# 28PinArduino.net
KiCad netlist of a schematic drawn in Altium Designer
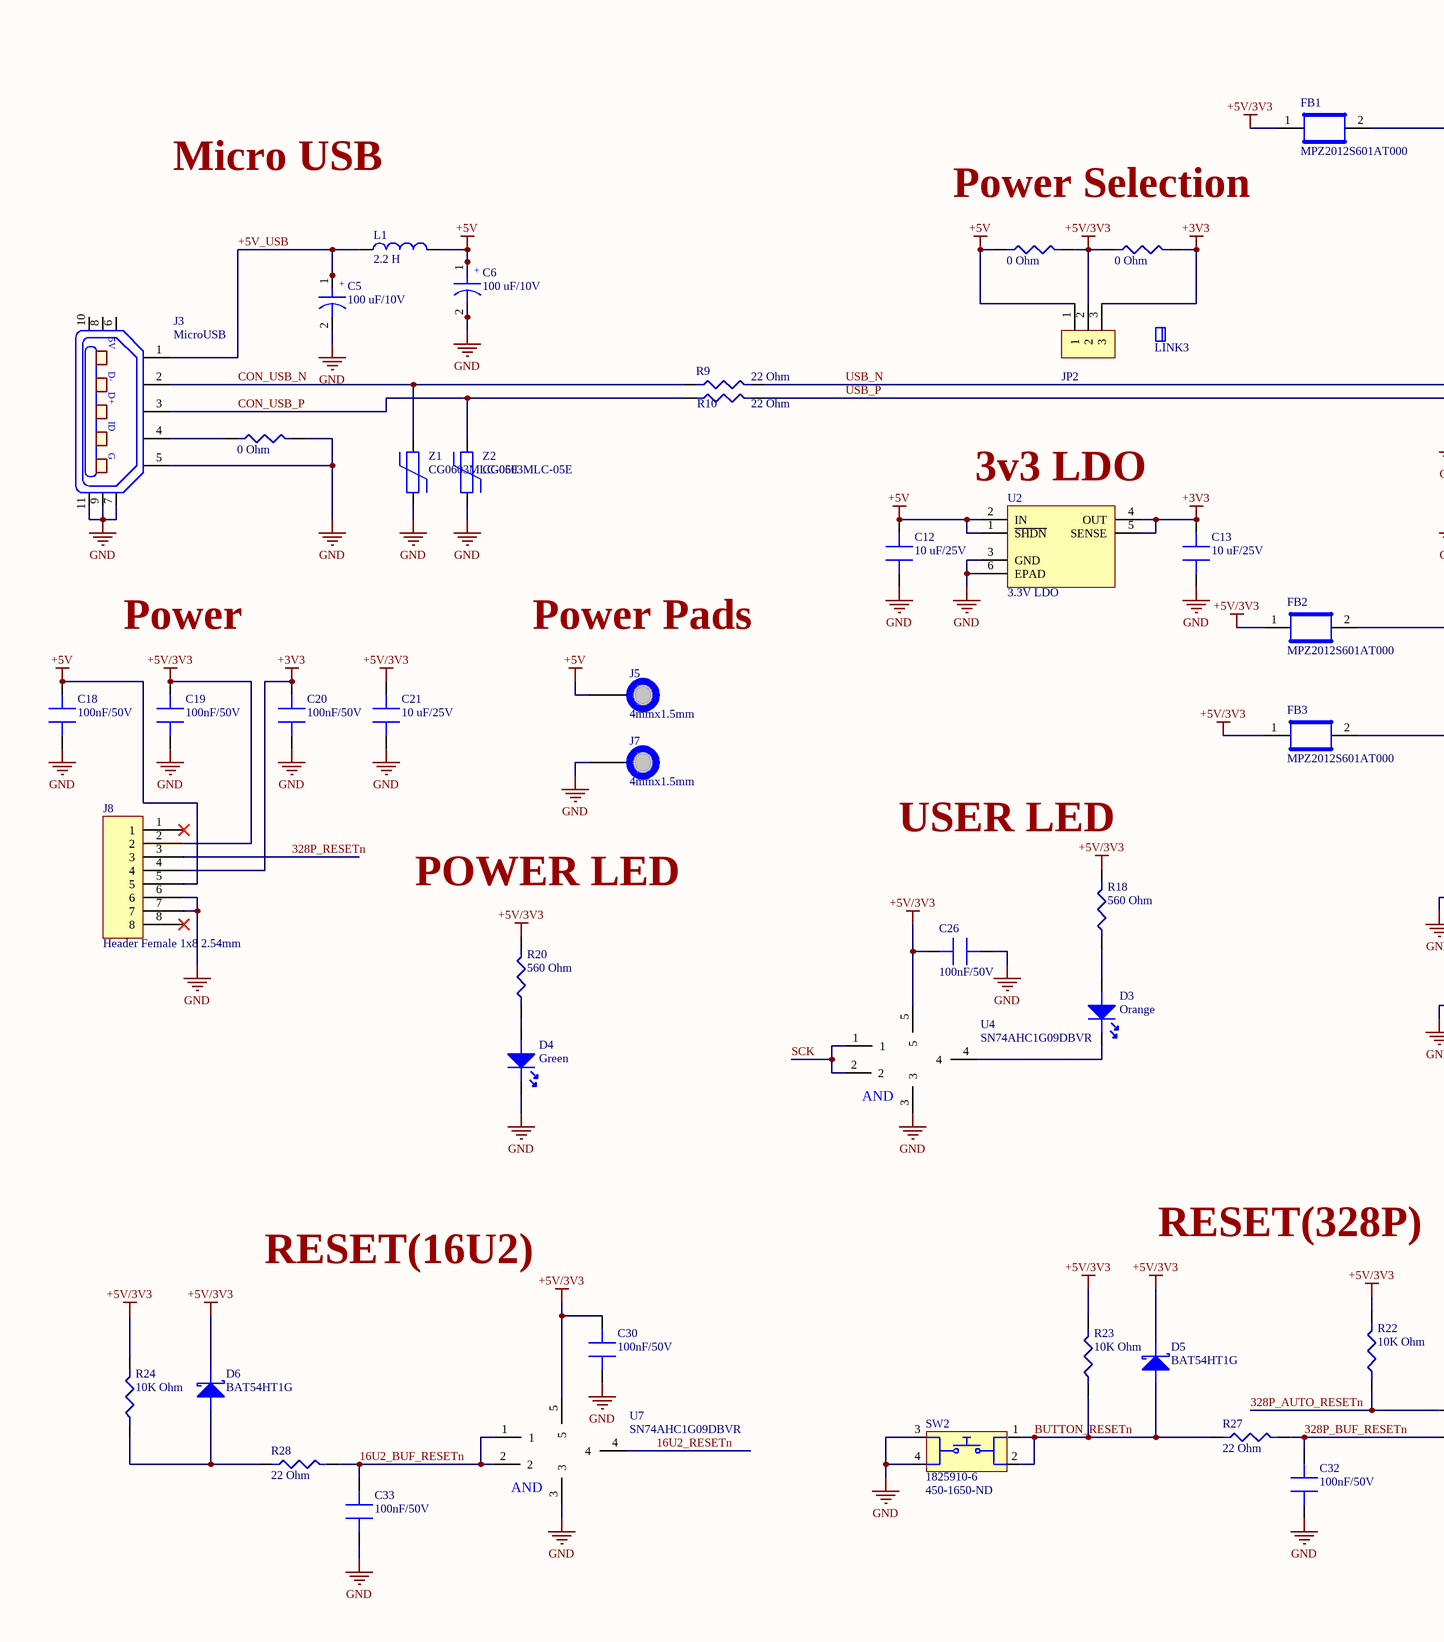
[diagram p0: 28PinArduino.SchDoc, left]
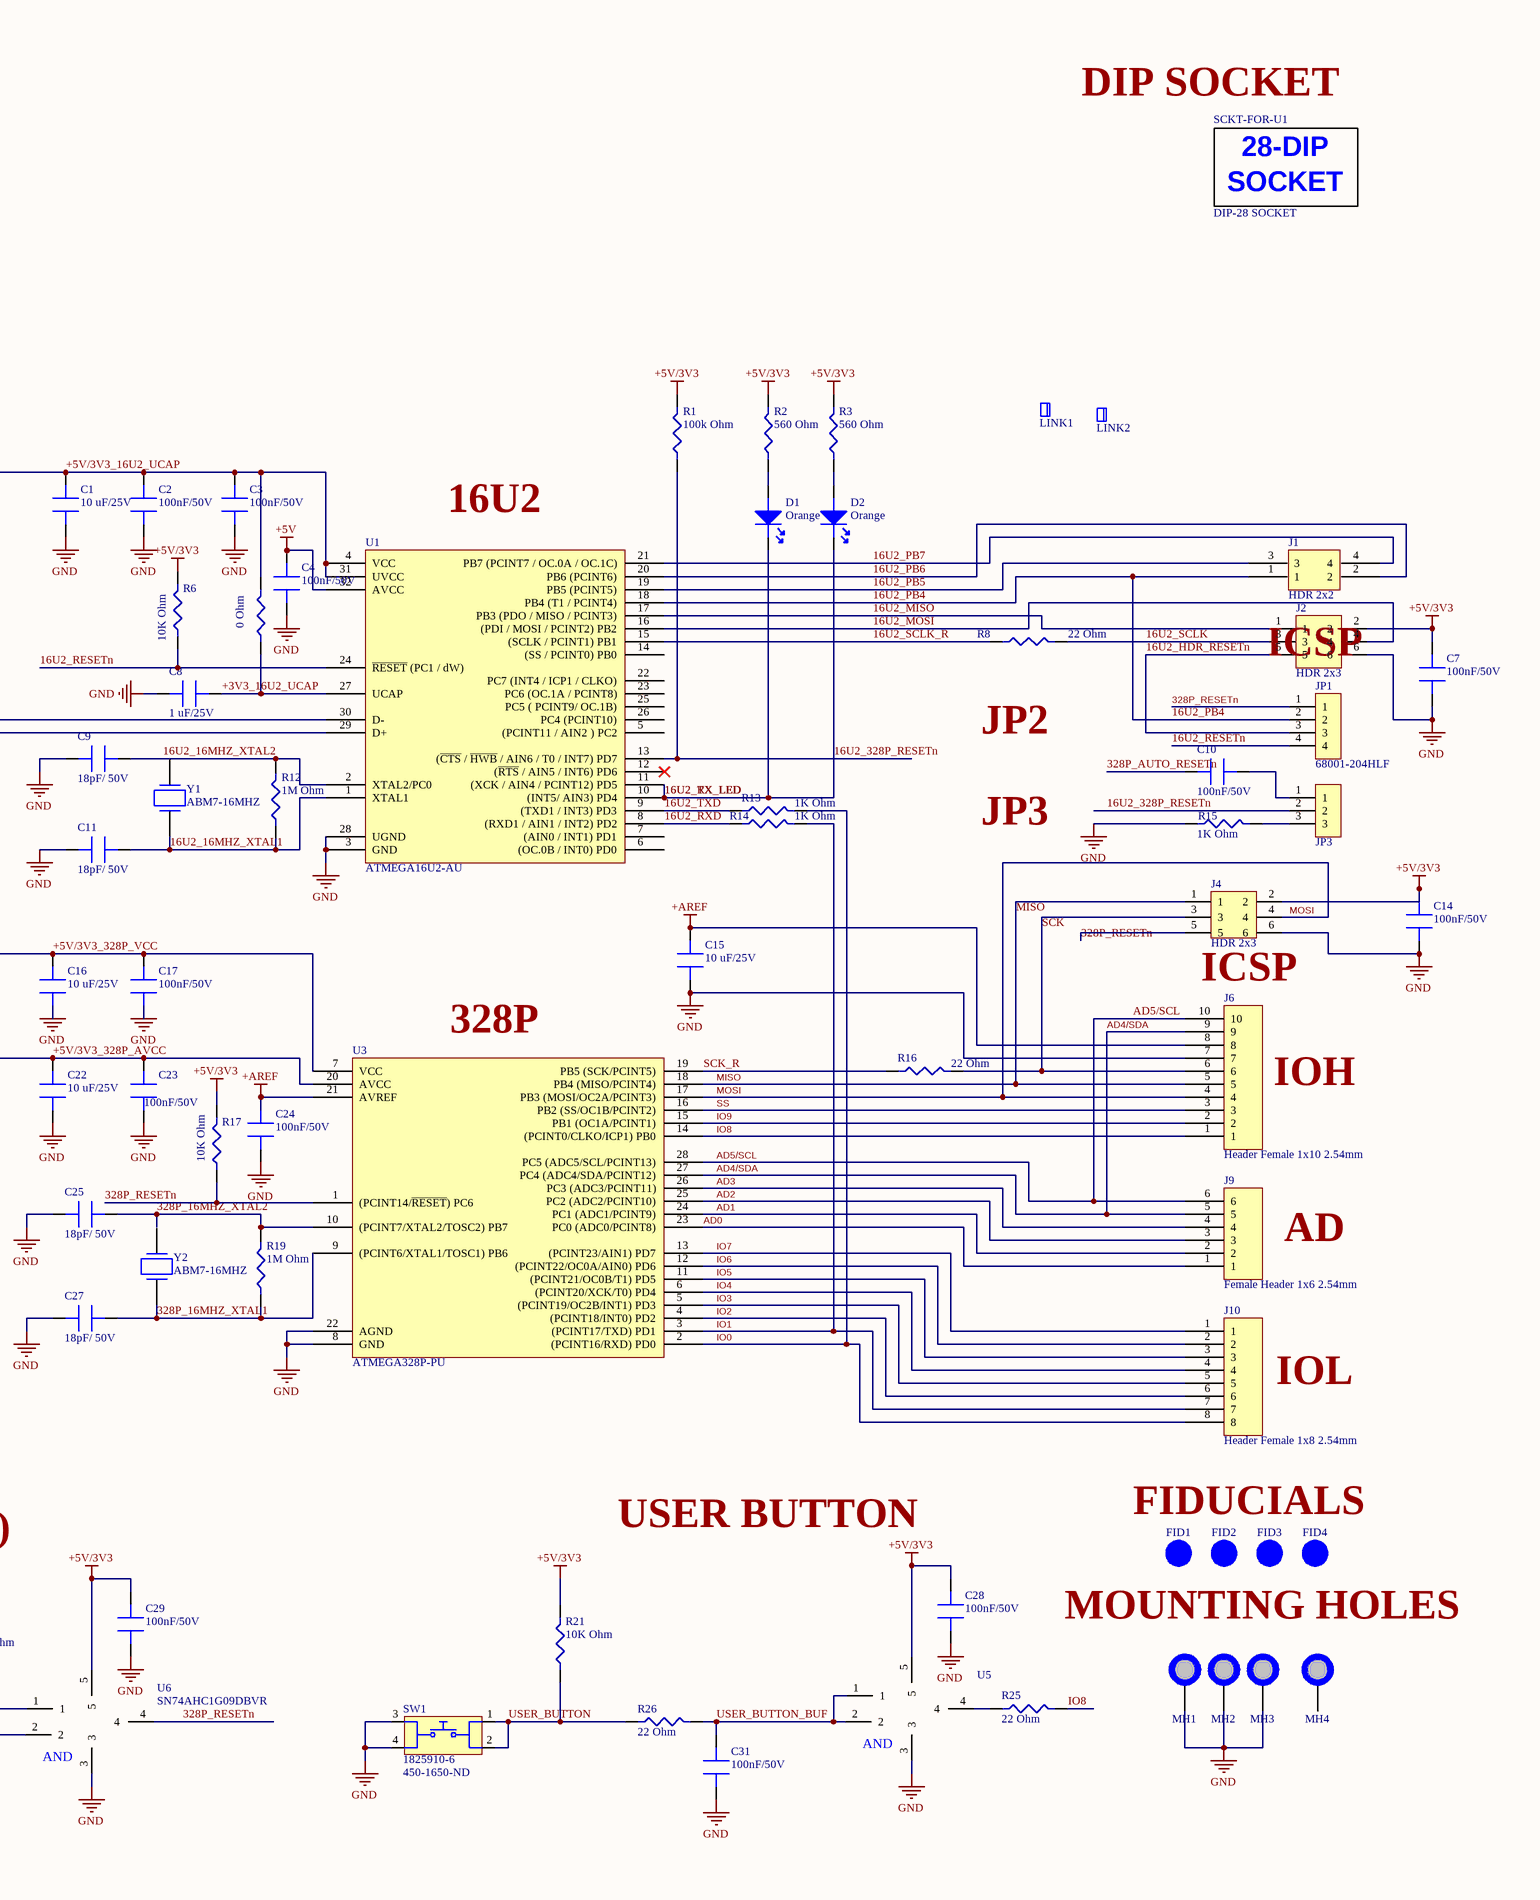
[diagram p1: 28PinArduino.SchDoc, right]

(export (version "E")
  (design (tool "Eeschema 10.0.6"))
  (components
    (comp (ref "C1")
      (value "10 uF/25V")
      (footprint "CAPC2012X14N")
      (fields
        (field (name "MANUFACTURER") "TDK")
        (field (name "MANUFACTURER PART NUMBER") "C2012X5R1E106K125AB")
        (field (name "TOLERANCE") "10%")
      )
      (libsource (lib "28PinArduino") (part "C2012X5R1E106K125AB"))
    )
    (comp (ref "C2")
      (value "100nF/50V")
      (footprint "CAPC2012X14N")
      (fields
        (field (name "MANUFACTURER") "TDK")
        (field (name "MANUFACTURER PART NUMBER") "C2012X7R1H104K085AA")
        (field (name "TOLERANCE") "10%")
      )
      (libsource (lib "28PinArduino") (part "C2012X7R1H104K085AA"))
    )
    (comp (ref "C3")
      (value "100nF/50V")
      (footprint "CAPC2012X14N")
      (fields
        (field (name "MANUFACTURER") "TDK")
        (field (name "MANUFACTURER PART NUMBER") "C2012X7R1H104K085AA")
        (field (name "TOLERANCE") "10%")
      )
      (libsource (lib "28PinArduino") (part "C2012X7R1H104K085AA"))
    )
    (comp (ref "C4")
      (value "100nF/50V")
      (footprint "CAPC2012X14N")
      (fields
        (field (name "MANUFACTURER") "TDK")
        (field (name "MANUFACTURER PART NUMBER") "C2012X7R1H104K085AA")
        (field (name "TOLERANCE") "10%")
      )
      (libsource (lib "28PinArduino") (part "C2012X7R1H104K085AA"))
    )
    (comp (ref "C5")
      (value "100 uF/10V")
      (footprint "C_ALU_C_SIZE")
      (description "Cap Aluminum 100uF 10V 20% (5 X 5.4mm) SMD 50mA 1000 hr 85°C T/R")
      (fields
        (field (name "MANUFACTURER") "Panasonic")
        (field (name "MANUFACTURER PART NUMBER") "EEE-1AA101WR")
      )
      (libsource (lib "28PinArduino") (part "EEE-1AA101WR"))
    )
    (comp (ref "C6")
      (value "100 uF/10V")
      (footprint "C_ALU_C_SIZE")
      (description "Cap Aluminum 100uF 10V 20% (5 X 5.4mm) SMD 50mA 1000 hr 85°C T/R")
      (fields
        (field (name "MANUFACTURER") "Panasonic")
        (field (name "MANUFACTURER PART NUMBER") "EEE-1AA101WR")
      )
      (libsource (lib "28PinArduino") (part "EEE-1AA101WR"))
    )
    (comp (ref "C7")
      (value "100nF/50V")
      (footprint "CAPC2012X14N")
      (fields
        (field (name "MANUFACTURER") "TDK")
        (field (name "MANUFACTURER PART NUMBER") "C2012X7R1H104K085AA")
        (field (name "TOLERANCE") "10%")
      )
      (libsource (lib "28PinArduino") (part "C2012X7R1H104K085AA"))
    )
    (comp (ref "C8")
      (value "1 uF/25V")
      (footprint "CAPC2012X14N")
      (fields
        (field (name "MANUFACTURER") "TDK")
        (field (name "MANUFACTURER PART NUMBER") "C2012X5R1E105K125AA")
        (field (name "TOLERANCE") "10%")
      )
      (libsource (lib "28PinArduino") (part "C2012X5R1E105K125AA"))
    )
    (comp (ref "C9")
      (value "18pF/ 50V")
      (footprint "CAPC2012X14N")
      (description "CAP CER 18PF 50V C0G/NP0 0805")
      (fields
        (field (name "MANUFACTURER") "KEMET")
        (field (name "MANUFACTURER PART NUMBER") "C0805C180J5GACTU")
      )
      (libsource (lib "28PinArduino") (part "C0805C180J5GACTU"))
    )
    (comp (ref "C10")
      (value "100nF/50V")
      (footprint "CAPC2012X14N")
      (fields
        (field (name "MANUFACTURER") "TDK")
        (field (name "MANUFACTURER PART NUMBER") "C2012X7R1H104K085AA")
        (field (name "TOLERANCE") "10%")
      )
      (libsource (lib "28PinArduino") (part "C2012X7R1H104K085AA"))
    )
    (comp (ref "C11")
      (value "18pF/ 50V")
      (footprint "CAPC2012X14N")
      (description "CAP CER 18PF 50V C0G/NP0 0805")
      (fields
        (field (name "MANUFACTURER") "KEMET")
        (field (name "MANUFACTURER PART NUMBER") "C0805C180J5GACTU")
      )
      (libsource (lib "28PinArduino") (part "C0805C180J5GACTU"))
    )
    (comp (ref "C12")
      (value "10 uF/25V")
      (footprint "CAPC2012X14N")
      (fields
        (field (name "MANUFACTURER") "TDK")
        (field (name "MANUFACTURER PART NUMBER") "C2012X5R1E106K125AB")
        (field (name "TOLERANCE") "10%")
      )
      (libsource (lib "28PinArduino") (part "C2012X5R1E106K125AB"))
    )
    (comp (ref "C13")
      (value "10 uF/25V")
      (footprint "CAPC2012X14N")
      (fields
        (field (name "MANUFACTURER") "TDK")
        (field (name "MANUFACTURER PART NUMBER") "C2012X5R1E106K125AB")
        (field (name "TOLERANCE") "10%")
      )
      (libsource (lib "28PinArduino") (part "C2012X5R1E106K125AB"))
    )
    (comp (ref "C14")
      (value "100nF/50V")
      (footprint "CAPC2012X14N")
      (fields
        (field (name "MANUFACTURER") "TDK")
        (field (name "MANUFACTURER PART NUMBER") "C2012X7R1H104K085AA")
        (field (name "TOLERANCE") "10%")
      )
      (libsource (lib "28PinArduino") (part "C2012X7R1H104K085AA"))
    )
    (comp (ref "C15")
      (value "10 uF/25V")
      (footprint "CAPC2012X14N")
      (fields
        (field (name "MANUFACTURER") "TDK")
        (field (name "MANUFACTURER PART NUMBER") "C2012X5R1E106K125AB")
        (field (name "TOLERANCE") "10%")
      )
      (libsource (lib "28PinArduino") (part "C2012X5R1E106K125AB"))
    )
    (comp (ref "C16")
      (value "10 uF/25V")
      (footprint "CAPC2012X14N")
      (fields
        (field (name "MANUFACTURER") "TDK")
        (field (name "MANUFACTURER PART NUMBER") "C2012X5R1E106K125AB")
        (field (name "TOLERANCE") "10%")
      )
      (libsource (lib "28PinArduino") (part "C2012X5R1E106K125AB"))
    )
    (comp (ref "C17")
      (value "100nF/50V")
      (footprint "CAPC2012X14N")
      (fields
        (field (name "MANUFACTURER") "TDK")
        (field (name "MANUFACTURER PART NUMBER") "C2012X7R1H104K085AA")
        (field (name "TOLERANCE") "10%")
      )
      (libsource (lib "28PinArduino") (part "C2012X7R1H104K085AA"))
    )
    (comp (ref "C18")
      (value "100nF/50V")
      (footprint "CAPC2012X14N")
      (fields
        (field (name "MANUFACTURER") "TDK")
        (field (name "MANUFACTURER PART NUMBER") "C2012X7R1H104K085AA")
        (field (name "TOLERANCE") "10%")
      )
      (libsource (lib "28PinArduino") (part "C2012X7R1H104K085AA"))
    )
    (comp (ref "C19")
      (value "100nF/50V")
      (footprint "CAPC2012X14N")
      (fields
        (field (name "MANUFACTURER") "TDK")
        (field (name "MANUFACTURER PART NUMBER") "C2012X7R1H104K085AA")
        (field (name "TOLERANCE") "10%")
      )
      (libsource (lib "28PinArduino") (part "C2012X7R1H104K085AA"))
    )
    (comp (ref "C20")
      (value "100nF/50V")
      (footprint "CAPC2012X14N")
      (fields
        (field (name "MANUFACTURER") "TDK")
        (field (name "MANUFACTURER PART NUMBER") "C2012X7R1H104K085AA")
        (field (name "TOLERANCE") "10%")
      )
      (libsource (lib "28PinArduino") (part "C2012X7R1H104K085AA"))
    )
    (comp (ref "C21")
      (value "10 uF/25V")
      (footprint "CAPC2012X14N")
      (fields
        (field (name "MANUFACTURER") "TDK")
        (field (name "MANUFACTURER PART NUMBER") "C2012X5R1E106K125AB")
        (field (name "TOLERANCE") "10%")
      )
      (libsource (lib "28PinArduino") (part "C2012X5R1E106K125AB"))
    )
    (comp (ref "C22")
      (value "10 uF/25V")
      (footprint "CAPC2012X14N")
      (fields
        (field (name "MANUFACTURER") "TDK")
        (field (name "MANUFACTURER PART NUMBER") "C2012X5R1E106K125AB")
        (field (name "TOLERANCE") "10%")
      )
      (libsource (lib "28PinArduino") (part "C2012X5R1E106K125AB"))
    )
    (comp (ref "C23")
      (value "100nF/50V")
      (footprint "CAPC2012X14N")
      (fields
        (field (name "MANUFACTURER") "TDK")
        (field (name "MANUFACTURER PART NUMBER") "C2012X7R1H104K085AA")
        (field (name "TOLERANCE") "10%")
      )
      (libsource (lib "28PinArduino") (part "C2012X7R1H104K085AA"))
    )
    (comp (ref "C24")
      (value "100nF/50V")
      (footprint "CAPC2012X14N")
      (fields
        (field (name "MANUFACTURER") "TDK")
        (field (name "MANUFACTURER PART NUMBER") "C2012X7R1H104K085AA")
        (field (name "TOLERANCE") "10%")
      )
      (libsource (lib "28PinArduino") (part "C2012X7R1H104K085AA"))
    )
    (comp (ref "C25")
      (value "18pF/ 50V")
      (footprint "CAPC2012X14N")
      (description "CAP CER 18PF 50V C0G/NP0 0805")
      (fields
        (field (name "MANUFACTURER") "KEMET")
        (field (name "MANUFACTURER PART NUMBER") "C0805C180J5GACTU")
      )
      (libsource (lib "28PinArduino") (part "C0805C180J5GACTU"))
    )
    (comp (ref "C26")
      (value "100nF/50V")
      (footprint "CAPC2012X14N")
      (fields
        (field (name "MANUFACTURER") "TDK")
        (field (name "MANUFACTURER PART NUMBER") "C2012X7R1H104K085AA")
        (field (name "TOLERANCE") "10%")
      )
      (libsource (lib "28PinArduino") (part "C2012X7R1H104K085AA"))
    )
    (comp (ref "C27")
      (value "18pF/ 50V")
      (footprint "CAPC2012X14N")
      (description "CAP CER 18PF 50V C0G/NP0 0805")
      (fields
        (field (name "MANUFACTURER") "KEMET")
        (field (name "MANUFACTURER PART NUMBER") "C0805C180J5GACTU")
      )
      (libsource (lib "28PinArduino") (part "C0805C180J5GACTU"))
    )
    (comp (ref "C28")
      (value "100nF/50V")
      (footprint "CAPC2012X14N")
      (fields
        (field (name "MANUFACTURER") "TDK")
        (field (name "MANUFACTURER PART NUMBER") "C2012X7R1H104K085AA")
        (field (name "TOLERANCE") "10%")
      )
      (libsource (lib "28PinArduino") (part "C2012X7R1H104K085AA"))
    )
    (comp (ref "C29")
      (value "100nF/50V")
      (footprint "CAPC2012X14N")
      (fields
        (field (name "MANUFACTURER") "TDK")
        (field (name "MANUFACTURER PART NUMBER") "C2012X7R1H104K085AA")
        (field (name "TOLERANCE") "10%")
      )
      (libsource (lib "28PinArduino") (part "C2012X7R1H104K085AA"))
    )
    (comp (ref "C30")
      (value "100nF/50V")
      (footprint "CAPC2012X14N")
      (fields
        (field (name "MANUFACTURER") "TDK")
        (field (name "MANUFACTURER PART NUMBER") "C2012X7R1H104K085AA")
        (field (name "TOLERANCE") "10%")
      )
      (libsource (lib "28PinArduino") (part "C2012X7R1H104K085AA"))
    )
    (comp (ref "C31")
      (value "100nF/50V")
      (footprint "CAPC2012X14N")
      (fields
        (field (name "MANUFACTURER") "TDK")
        (field (name "MANUFACTURER PART NUMBER") "C2012X7R1H104K085AA")
        (field (name "TOLERANCE") "10%")
      )
      (libsource (lib "28PinArduino") (part "C2012X7R1H104K085AA"))
    )
    (comp (ref "C32")
      (value "100nF/50V")
      (footprint "CAPC2012X14N")
      (fields
        (field (name "MANUFACTURER") "TDK")
        (field (name "MANUFACTURER PART NUMBER") "C2012X7R1H104K085AA")
        (field (name "TOLERANCE") "10%")
      )
      (libsource (lib "28PinArduino") (part "C2012X7R1H104K085AA"))
    )
    (comp (ref "C33")
      (value "100nF/50V")
      (footprint "CAPC2012X14N")
      (fields
        (field (name "MANUFACTURER") "TDK")
        (field (name "MANUFACTURER PART NUMBER") "C2012X7R1H104K085AA")
        (field (name "TOLERANCE") "10%")
      )
      (libsource (lib "28PinArduino") (part "C2012X7R1H104K085AA"))
    )
    (comp (ref "D1")
      (value "Orange")
      (footprint "LED0603")
      (description "OSRAM - LO L29K-H2K1-24-Z - SMARTLED 0603 ORANGE")
      (fields
        (field (name "MANUFACTURER") "Osram Opto")
        (field (name "MANUFACTURER PART NUMBER") "LOL29K-H2K1-24-Z")
      )
      (libsource (lib "28PinArduino") (part "LOL29K-H2K1-24-Z"))
    )
    (comp (ref "D2")
      (value "Orange")
      (footprint "LED0603")
      (description "OSRAM - LO L29K-H2K1-24-Z - SMARTLED 0603 ORANGE")
      (fields
        (field (name "MANUFACTURER") "Osram Opto")
        (field (name "MANUFACTURER PART NUMBER") "LOL29K-H2K1-24-Z")
      )
      (libsource (lib "28PinArduino") (part "LOL29K-H2K1-24-Z"))
    )
    (comp (ref "D3")
      (value "Orange")
      (footprint "LED0603")
      (description "OSRAM - LO L29K-H2K1-24-Z - SMARTLED 0603 ORANGE")
      (fields
        (field (name "MANUFACTURER") "Osram Opto")
        (field (name "MANUFACTURER PART NUMBER") "LOL29K-H2K1-24-Z")
      )
      (libsource (lib "28PinArduino") (part "LOL29K-H2K1-24-Z"))
    )
    (comp (ref "D4")
      (value "Green")
      (footprint "LED0603")
      (description "LED Uni-Color Green 572nm 2-Pin Chip 0603(1608Metric) T/R")
      (fields
        (field (name "MANUFACTURER") "Osram Opto")
        (field (name "MANUFACTURER PART NUMBER") "LGL29K-G2J1-24-Z")
      )
      (libsource (lib "28PinArduino") (part "LGL29K-G2J1-24-Z"))
    )
    (comp (ref "D5")
      (value "BAT54HT1G")
      (footprint "Diode_SOD323")
      (description "Small Signal Schottky Diode, Single, 30 V, 200 mA, 800 mV, 600 mA, 150 C ;RoHS Compliant: Yes")
      (fields (field (name "MANUFACTURER") "ON Semiconductor / Fairchild"))
      (libsource (lib "28PinArduino") (part "BAT54HT1G"))
    )
    (comp (ref "D6")
      (value "BAT54HT1G")
      (footprint "Diode_SOD323")
      (description "Small Signal Schottky Diode, Single, 30 V, 200 mA, 800 mV, 600 mA, 150 C ;RoHS Compliant: Yes")
      (fields (field (name "MANUFACTURER") "ON Semiconductor / Fairchild"))
      (libsource (lib "28PinArduino") (part "BAT54HT1G"))
    )
    (comp (ref "FB1")
      (value "MPZ2012S601AT000")
      (footprint "CAPC2012X14N")
      (description "FERRITE BEAD 600 OHM 0805 1LN")
      (fields (field (name "MANUFACTURER") "TDK"))
      (libsource (lib "28PinArduino") (part "MPZ2012S601AT000"))
    )
    (comp (ref "FB2")
      (value "MPZ2012S601AT000")
      (footprint "CAPC2012X14N")
      (description "FERRITE BEAD 600 OHM 0805 1LN")
      (fields (field (name "MANUFACTURER") "TDK"))
      (libsource (lib "28PinArduino") (part "MPZ2012S601AT000"))
    )
    (comp (ref "FB3")
      (value "MPZ2012S601AT000")
      (footprint "CAPC2012X14N")
      (description "FERRITE BEAD 600 OHM 0805 1LN")
      (fields (field (name "MANUFACTURER") "TDK"))
      (libsource (lib "28PinArduino") (part "MPZ2012S601AT000"))
    )
    (comp (ref "FID1")
      (value "FID_1mm")
      (footprint "FID_40X1_20D")
      (description "Fiducial 40 mil Diameter 120mil Mask")
      (libsource (lib "28PinArduino") (part "FID_1mm"))
    )
    (comp (ref "FID2")
      (value "FID_1mm")
      (footprint "FID_40X1_20D")
      (description "Fiducial 40 mil Diameter 120mil Mask")
      (libsource (lib "28PinArduino") (part "FID_1mm"))
    )
    (comp (ref "FID3")
      (value "FID_1mm")
      (footprint "FID_40X1_20D")
      (description "Fiducial 40 mil Diameter 120mil Mask")
      (libsource (lib "28PinArduino") (part "FID_1mm"))
    )
    (comp (ref "FID4")
      (value "FID_1mm")
      (footprint "FID_40X1_20D")
      (description "Fiducial 40 mil Diameter 120mil Mask")
      (libsource (lib "28PinArduino") (part "FID_1mm"))
    )
    (comp (ref "J1")
      (value "HDR 2x2")
      (fields
        (field (name "MANUFACTURER") "Amphenol ICC / FCI")
        (field (name "MANUFACTURER PART NUMBER") "68602-204HLF")
      )
      (libsource (lib "28PinArduino") (part "68602-204HLF"))
    )
    (comp (ref "J2")
      (value "HDR 2x3")
      (footprint "DIP6")
      (description "CONN HEADER 6POS .100 STR 30AU")
      (fields
        (field (name "MANUFACTURER") "Amphenol FCI")
        (field (name "MANUFACTURER PART NUMBER") "67997-106HLF")
      )
      (libsource (lib "") (part "67997-106HLF_1"))
    )
    (comp (ref "J3")
      (value "MicroUSB")
      (footprint "microUSB")
      (description "CONN USB MICRO B RECPT SMT R/A")
      (fields
        (field (name "MANUFACTURER") "Amphenol FCI")
        (field (name "MANUFACTURER PART NUMBER") "10118193-0001LF")
      )
      (libsource (lib "28PinArduino") (part "10118193-0001LF"))
    )
    (comp (ref "J4")
      (value "HDR 2x3")
      (footprint "DIP6")
      (description "CONN HEADER 6POS .100 STR 30AU")
      (fields
        (field (name "MANUFACTURER") "Amphenol FCI")
        (field (name "MANUFACTURER PART NUMBER") "67997-106HLF")
      )
      (libsource (lib "28PinArduino") (part "67997-106HLF"))
    )
    (comp (ref "J5")
      (value "4mmx1.5mm")
      (footprint "PAD_WITH_HOLE")
      (description "Pad with a hole")
      (libsource (lib "28PinArduino") (part "PAD_WITH_HOLE"))
    )
    (comp (ref "J6")
      (value "Header Female 1x10 2.54mm")
      (footprint "DIP20")
      (fields (field (name "MANUFACTURER") "Harwin") (field (name "MANUFACTURER PART NUMBER") "M20-7821046"))
      (libsource (lib "28PinArduino") (part "M20-7821046"))
    )
    (comp (ref "J7")
      (value "4mmx1.5mm")
      (footprint "PAD_WITH_HOLE")
      (description "Pad with a hole")
      (libsource (lib "28PinArduino") (part "PAD_WITH_HOLE"))
    )
    (comp (ref "J8")
      (value "Header Female 1x8 2.54mm")
      (footprint "DIP16")
      (description "2.54mm (0.1\") Pitch SIL Vertical PC Tail Socket Assembly, selective gold + tin, 8 contacts")
      (fields (field (name "MANUFACTURER") "Harwin") (field (name "MANUFACTURER PART NUMBER") "M20-7820842"))
      (libsource (lib "") (part "M20-7820842_1"))
    )
    (comp (ref "J9")
      (value "Female Header 1x6 2.54mm")
      (footprint "DIP12")
      (description "06-WAY SIL VERT SOCKET L/FREE")
      (fields (field (name "MANUFACTURER") "Harwin") (field (name "MANUFACTURER PART NUMBER") "M20-7820646"))
      (libsource (lib "28PinArduino") (part "M20-7820646"))
    )
    (comp (ref "J10")
      (value "Header Female 1x8 2.54mm")
      (footprint "DIP16")
      (description "2.54mm (0.1\") Pitch SIL Vertical PC Tail Socket Assembly, selective gold + tin, 8 contacts")
      (fields (field (name "MANUFACTURER") "Harwin") (field (name "MANUFACTURER PART NUMBER") "M20-7820842"))
      (libsource (lib "28PinArduino") (part "M20-7820842"))
    )
    (comp (ref "JP1")
      (value "68001-204HLF")
      (footprint "DIP1x4")
      (description "CONN HEADER VERT 4POS 2.54MM")
      (fields (field (name "MANUFACTURER") "Amphenol FCI"))
      (libsource (lib "28PinArduino") (part "68001-204HLF"))
    )
    (comp (ref "JP2")
      (value "68000-103HLF")
      (footprint "DIP1x3")
      (fields (field (name "MANUFACTURER") "Amphenol ICC"))
      (libsource (lib "28PinArduino") (part "68000-103HLF"))
    )
    (comp (ref "JP3")
      (value "68000-103HLF")
      (footprint "DIP1x3")
      (fields (field (name "MANUFACTURER") "Amphenol ICC"))
      (libsource (lib "") (part "68000-103HLF_1"))
    )
    (comp (ref "L1")
      (value "2.2 H")
      (footprint "L1210")
      (description "FIXED IND 2.2UH 2A 80 MOHM SMD")
      (fields
        (field (name "MANUFACTURER") "KEMET")
        (field (name "MANUFACTURER PART NUMBER") "L1210R2R2MDWIT")
      )
      (libsource (lib "28PinArduino") (part "L1210R2R2MDWIT"))
    )
    (comp (ref "LINK1")
      (value "Link")
      (description "CONN JUMPER SHORTING .100\" GOLD")
      (fields
        (field (name "MANUFACTURER") "Sullins")
        (field (name "MANUFACTURER PART NUMBER") "QPC02SXGN-RC")
      )
      (libsource (lib "28PinArduino") (part "QPC02SXGN-RC"))
    )
    (comp (ref "LINK2")
      (value "Link")
      (description "CONN JUMPER SHORTING .100\" GOLD")
      (fields
        (field (name "MANUFACTURER") "Sullins")
        (field (name "MANUFACTURER PART NUMBER") "QPC02SXGN-RC")
      )
      (libsource (lib "28PinArduino") (part "QPC02SXGN-RC"))
    )
    (comp (ref "LINK3")
      (value "Link")
      (description "CONN JUMPER SHORTING .100\" GOLD")
      (fields
        (field (name "MANUFACTURER") "Sullins")
        (field (name "MANUFACTURER PART NUMBER") "QPC02SXGN-RC")
      )
      (libsource (lib "28PinArduino") (part "QPC02SXGN-RC"))
    )
    (comp (ref "MH1")
      (value "MH_7.4MMC_3.2")
      (footprint "MH_7.4mm_3.2mm")
      (description "Mounting Hole 7.4mm diameter, 3.2 mm drill")
      (libsource (lib "28PinArduino") (part "MH_7.4MMC_3.2"))
    )
    (comp (ref "MH2")
      (value "MH_7.4MMC_3.2")
      (footprint "MH_7.4mm_3.2mm")
      (description "Mounting Hole 7.4mm diameter, 3.2 mm drill")
      (libsource (lib "28PinArduino") (part "MH_7.4MMC_3.2"))
    )
    (comp (ref "MH3")
      (value "MH_7.4MMC_3.2")
      (footprint "MH_7.4mm_3.2mm")
      (description "Mounting Hole 7.4mm diameter, 3.2 mm drill")
      (libsource (lib "28PinArduino") (part "MH_7.4MMC_3.2"))
    )
    (comp (ref "MH4")
      (value "MH_7.4MMC_3")
      (footprint "MH_7.4mm_3.2mm")
      (description "Mounting Hole Non Copper 7.4mm diameter 3mm drill NPTH")
      (libsource (lib "28PinArduino") (part "MH_7.4MMNC_3.2MMD"))
    )
    (comp (ref "R1")
      (value "100k Ohm")
      (footprint "RESC2012X06N")
      (description "YAGEO         RC0805FR-07100KL            RES, THICK FILM, 100K, 1%, 0.125W, 0805, REEL")
      (fields
        (field (name "MANUFACTURER") "Yageo")
        (field (name "MANUFACTURER PART NUMBER") "RC0805FR-07100KL")
      )
      (libsource (lib "28PinArduino") (part "RC0805FR-07100KL (2)"))
    )
    (comp (ref "R2")
      (value "560 Ohm")
      (footprint "RESC2012X06N")
      (description "Surface Mount Thick Film Resistor, RC Series, 560 ohm, 125 mW, - 1%, 150 V, 0805 [2012 Metric]")
      (fields
        (field (name "MANUFACTURER") "Yageo")
        (field (name "MANUFACTURER PART NUMBER") "RC0805FR-07560RL")
      )
      (libsource (lib "28PinArduino") (part "RC0805FR-07560RL"))
    )
    (comp (ref "R3")
      (value "560 Ohm")
      (footprint "RESC2012X06N")
      (description "Surface Mount Thick Film Resistor, RC Series, 560 ohm, 125 mW, - 1%, 150 V, 0805 [2012 Metric]")
      (fields
        (field (name "MANUFACTURER") "Yageo")
        (field (name "MANUFACTURER PART NUMBER") "RC0805FR-07560RL")
      )
      (libsource (lib "28PinArduino") (part "RC0805FR-07560RL"))
    )
    (comp (ref "R4")
      (value "0 Ohm")
      (description "Surface Mount Thick Film Resistor, RC Series, 125 mW, - 5%, 150 V, 0805 [2012 Metric]")
      (fields
        (field (name "MANUFACTURER") "Yageo")
        (field (name "MANUFACTURER PART NUMBER") "RC0805JR-070RL")
      )
      (libsource (lib "28PinArduino") (part "RC0805JR-070RL"))
    )
    (comp (ref "R5")
      (value "0 Ohm")
      (description "Surface Mount Thick Film Resistor, RC Series, 125 mW, - 5%, 150 V, 0805 [2012 Metric]")
      (fields
        (field (name "MANUFACTURER") "Yageo")
        (field (name "MANUFACTURER PART NUMBER") "RC0805JR-070RL")
      )
      (libsource (lib "28PinArduino") (part "RC0805JR-070RL"))
    )
    (comp (ref "R6")
      (value "10K Ohm")
      (footprint "RESC2012X06N")
      (description "YAGEO         RC0805FR-07100KL            RES, THICK FILM, 100K, 1%, 0.125W, 0805, REEL")
      (fields
        (field (name "MANUFACTURER") "Yageo")
        (field (name "MANUFACTURER PART NUMBER") "RC0805FR-07100KL")
      )
      (libsource (lib "28PinArduino") (part "RC0805FR-07100KL"))
    )
    (comp (ref "R7")
      (value "0 Ohm")
      (footprint "RESC2012X06N")
      (description "Surface Mount Thick Film Resistor, RC Series, 125 mW, - 5%, 150 V, 0805 [2012 Metric]")
      (fields
        (field (name "MANUFACTURER") "Yageo")
        (field (name "MANUFACTURER PART NUMBER") "RC0805JR-070RL")
      )
      (libsource (lib "28PinArduino") (part "RC0805JR-070RL"))
    )
    (comp (ref "R8")
      (value "22 Ohm")
      (footprint "RESC2012X06N")
      (description "YAGEO         RC0805FR-072R2L             RES, THICK FILM, 2R2, 1%, 0.125W, 0805")
      (fields
        (field (name "MANUFACTURER") "Yageo")
        (field (name "MANUFACTURER PART NUMBER") "RC0805FR-072R2L")
      )
      (libsource (lib "28PinArduino") (part "RC0805FR-072R2L"))
    )
    (comp (ref "R9")
      (value "22 Ohm")
      (footprint "RESC2012X06N")
      (description "YAGEO         RC0805FR-072R2L             RES, THICK FILM, 2R2, 1%, 0.125W, 0805")
      (fields
        (field (name "MANUFACTURER") "Yageo")
        (field (name "MANUFACTURER PART NUMBER") "RC0805FR-072R2L")
      )
      (libsource (lib "28PinArduino") (part "RC0805FR-072R2L"))
    )
    (comp (ref "R10")
      (value "22 Ohm")
      (footprint "RESC2012X06N")
      (description "YAGEO         RC0805FR-072R2L             RES, THICK FILM, 2R2, 1%, 0.125W, 0805")
      (fields
        (field (name "MANUFACTURER") "Yageo")
        (field (name "MANUFACTURER PART NUMBER") "RC0805FR-072R2L")
      )
      (libsource (lib "28PinArduino") (part "RC0805FR-072R2L"))
    )
    (comp (ref "R11")
      (value "0 Ohm")
      (footprint "RESC2012X06N")
      (description "Surface Mount Thick Film Resistor, RC Series, 125 mW, - 5%, 150 V, 0805 [2012 Metric]")
      (fields
        (field (name "MANUFACTURER") "Yageo")
        (field (name "MANUFACTURER PART NUMBER") "RC0805JR-070RL")
      )
      (libsource (lib "28PinArduino") (part "RC0805JR-070RL"))
    )
    (comp (ref "R12")
      (value "1M Ohm")
      (footprint "RESC2012X06N")
      (description "Res Thick Film 0805 1M Ohm 1% 0.125W(1/8W) ±100ppm/C Epoxy SMD T/R")
      (fields
        (field (name "MANUFACTURER") "Yageo Phycomp")
        (field (name "MANUFACTURER PART NUMBER") "RC0805FR-071ML")
      )
      (libsource (lib "28PinArduino") (part "RC0805FR-071ML"))
    )
    (comp (ref "R13")
      (value "1K Ohm")
      (footprint "RESC2012X06N")
      (fields
        (field (name "MANUFACTURER") "Yageo")
        (field (name "MANUFACTURER PART NUMBER") "RC0805FR-071KL")
        (field (name "TOLERANCE") "1%")
      )
      (libsource (lib "28PinArduino") (part "RC0805FR-071KL"))
    )
    (comp (ref "R14")
      (value "1K Ohm")
      (footprint "RESC2012X06N")
      (fields
        (field (name "MANUFACTURER") "Yageo")
        (field (name "MANUFACTURER PART NUMBER") "RC0805FR-071KL")
        (field (name "TOLERANCE") "1%")
      )
      (libsource (lib "28PinArduino") (part "RC0805FR-071KL"))
    )
    (comp (ref "R15")
      (value "1K Ohm")
      (footprint "RESC2012X06N")
      (fields
        (field (name "MANUFACTURER") "Yageo")
        (field (name "MANUFACTURER PART NUMBER") "RC0805FR-071KL")
        (field (name "TOLERANCE") "1%")
      )
      (libsource (lib "28PinArduino") (part "RC0805FR-071KL"))
    )
    (comp (ref "R16")
      (value "22 Ohm")
      (footprint "RESC2012X06N")
      (description "YAGEO         RC0805FR-072R2L             RES, THICK FILM, 2R2, 1%, 0.125W, 0805")
      (fields
        (field (name "MANUFACTURER") "Yageo")
        (field (name "MANUFACTURER PART NUMBER") "RC0805FR-072R2L")
      )
      (libsource (lib "28PinArduino") (part "RC0805FR-072R2L"))
    )
    (comp (ref "R17")
      (value "10K Ohm")
      (footprint "RESC2012X06N")
      (description "YAGEO         RC0805FR-07100KL            RES, THICK FILM, 100K, 1%, 0.125W, 0805, REEL")
      (fields
        (field (name "MANUFACTURER") "Yageo")
        (field (name "MANUFACTURER PART NUMBER") "RC0805FR-07100KL")
      )
      (libsource (lib "28PinArduino") (part "RC0805FR-07100KL"))
    )
    (comp (ref "R18")
      (value "560 Ohm")
      (footprint "RESC2012X06N")
      (description "Surface Mount Thick Film Resistor, RC Series, 560 ohm, 125 mW, - 1%, 150 V, 0805 [2012 Metric]")
      (fields
        (field (name "MANUFACTURER") "Yageo")
        (field (name "MANUFACTURER PART NUMBER") "RC0805FR-07560RL")
      )
      (libsource (lib "28PinArduino") (part "RC0805FR-07560RL"))
    )
    (comp (ref "R19")
      (value "1M Ohm")
      (footprint "RESC2012X06N")
      (description "Res Thick Film 0805 1M Ohm 1% 0.125W(1/8W) ±100ppm/C Epoxy SMD T/R")
      (fields
        (field (name "MANUFACTURER") "Yageo Phycomp")
        (field (name "MANUFACTURER PART NUMBER") "RC0805FR-071ML")
      )
      (libsource (lib "28PinArduino") (part "RC0805FR-071ML"))
    )
    (comp (ref "R20")
      (value "560 Ohm")
      (footprint "RESC2012X06N")
      (description "Surface Mount Thick Film Resistor, RC Series, 560 ohm, 125 mW, - 1%, 150 V, 0805 [2012 Metric]")
      (fields
        (field (name "MANUFACTURER") "Yageo")
        (field (name "MANUFACTURER PART NUMBER") "RC0805FR-07560RL")
      )
      (libsource (lib "28PinArduino") (part "RC0805FR-07560RL"))
    )
    (comp (ref "R21")
      (value "10K Ohm")
      (footprint "RESC2012X06N")
      (description "RES SMD 10K OHM 1% 1/8W 0805")
      (fields
        (field (name "MANUFACTURER") "Yageo")
        (field (name "MANUFACTURER PART NUMBER") "RC0805FR-0710KL")
      )
      (libsource (lib "28PinArduino") (part "RC0805FR-0710KL"))
    )
    (comp (ref "R22")
      (value "10K Ohm")
      (footprint "RESC2012X06N")
      (description "YAGEO         RC0805FR-07100KL            RES, THICK FILM, 100K, 1%, 0.125W, 0805, REEL")
      (fields
        (field (name "MANUFACTURER") "Yageo")
        (field (name "MANUFACTURER PART NUMBER") "RC0805FR-07100KL")
      )
      (libsource (lib "28PinArduino") (part "RC0805FR-07100KL"))
    )
    (comp (ref "R23")
      (value "10K Ohm")
      (footprint "RESC2012X06N")
      (description "RES SMD 10K OHM 1% 1/8W 0805")
      (fields
        (field (name "MANUFACTURER") "Yageo")
        (field (name "MANUFACTURER PART NUMBER") "RC0805FR-0710KL")
      )
      (libsource (lib "28PinArduino") (part "RC0805FR-0710KL"))
    )
    (comp (ref "R24")
      (value "10K Ohm")
      (footprint "RESC2012X06N")
      (description "RES SMD 10K OHM 1% 1/8W 0805")
      (fields
        (field (name "MANUFACTURER") "Yageo")
        (field (name "MANUFACTURER PART NUMBER") "RC0805FR-0710KL")
      )
      (libsource (lib "28PinArduino") (part "RC0805FR-0710KL"))
    )
    (comp (ref "R25")
      (value "22 Ohm")
      (footprint "RESC2012X06N")
      (description "YAGEO         RC0805FR-072R2L             RES, THICK FILM, 2R2, 1%, 0.125W, 0805")
      (fields
        (field (name "MANUFACTURER") "Yageo")
        (field (name "MANUFACTURER PART NUMBER") "RC0805FR-072R2L")
      )
      (libsource (lib "28PinArduino") (part "RC0805FR-072R2L"))
    )
    (comp (ref "R26")
      (value "22 Ohm")
      (footprint "RESC2012X06N")
      (description "YAGEO         RC0805FR-072R2L             RES, THICK FILM, 2R2, 1%, 0.125W, 0805")
      (fields
        (field (name "MANUFACTURER") "Yageo")
        (field (name "MANUFACTURER PART NUMBER") "RC0805FR-072R2L")
      )
      (libsource (lib "28PinArduino") (part "RC0805FR-072R2L"))
    )
    (comp (ref "R27")
      (value "22 Ohm")
      (footprint "RESC2012X06N")
      (description "YAGEO         RC0805FR-072R2L             RES, THICK FILM, 2R2, 1%, 0.125W, 0805")
      (fields
        (field (name "MANUFACTURER") "Yageo")
        (field (name "MANUFACTURER PART NUMBER") "RC0805FR-072R2L")
      )
      (libsource (lib "28PinArduino") (part "RC0805FR-072R2L"))
    )
    (comp (ref "R28")
      (value "22 Ohm")
      (footprint "RESC2012X06N")
      (description "YAGEO         RC0805FR-072R2L             RES, THICK FILM, 2R2, 1%, 0.125W, 0805")
      (fields
        (field (name "MANUFACTURER") "Yageo")
        (field (name "MANUFACTURER PART NUMBER") "RC0805FR-072R2L")
      )
      (libsource (lib "28PinArduino") (part "RC0805FR-072R2L"))
    )
    (comp (ref "SCKT-FOR-U1")
      (value "DIP-28 SOCKET")
      (footprint "28_DIP_SOCKET")
      (description "Conn IC DIP Socket 28POS Tin")
      (fields (field (name "MANUFACTURER") "3M") (field (name "MANUFACTURER PART NUMBER") "7010501790"))
      (libsource (lib "28PinArduino") (part "7010501790"))
    )
    (comp (ref "SW1")
      (value "1825910-6")
      (footprint "DIP4")
      (description "SWITCH TACTILE SPST-NO 0.05A 24V")
      (fields
        (field (name "MANUFACTURER") "TE Connectivity Alcoswitch")
        (field (name "SUPPLIER PART NUMBER 1") "450-1650-ND")
      )
      (libsource (lib "28PinArduino") (part "1825910-6"))
    )
    (comp (ref "SW2")
      (value "1825910-6")
      (footprint "DIP4")
      (description "SWITCH TACTILE SPST-NO 0.05A 24V")
      (fields
        (field (name "MANUFACTURER") "TE Connectivity Alcoswitch")
        (field (name "SUPPLIER PART NUMBER 1") "450-1650-ND")
      )
      (libsource (lib "28PinArduino") (part "1825910-6"))
    )
    (comp (ref "U1")
      (value "ATMEGA16U2-AU")
      (footprint "Quad32")
      (description "MICROCHIP - ATMEGA16U2-AU - MCU, 8BIT, MEGAAVR, 16MHZ, TQFP-32")
      (fields (field (name "MANUFACTURER") "Microchip / Atmel"))
      (libsource (lib "28PinArduino") (part "ATMEGA16U2-AU"))
    )
    (comp (ref "U2")
      (value "3.3V LDO")
      (footprint "SOT223-6")
      (description "IC REG LINEAR 3.3V 1.5A SOT223-6")
      (fields
        (field (name "MANUFACTURER") "Texas Instruments")
        (field (name "MANUFACTURER PART NUMBER") "TL1963A-33DCQR")
      )
      (libsource (lib "28PinArduino") (part "TL1963A-33DCQR"))
    )
    (comp (ref "U3")
      (value "ATMEGA328P-PU")
      (footprint "DIP28")
      (description "ATMEGA328P-PU; 8 bit Microcontroller AVR 20MHz 1; 32kb Flash; 2kb RAM; I2C SPI 2")
      (fields (field (name "MANUFACTURER") "Microchip"))
      (libsource (lib "28PinArduino") (part "ATMEGA328P-PU"))
    )
    (comp (ref "U4")
      (value "SN74AHC1G09DBVR")
      (footprint "DBV_SOD235")
      (description "TEXAS INSTRUMENTS - SN74AHC1G09DBVR - AND Gate, 74AHC1G09, 2 Input, 2 V to 5.5 V, SOT-23-5")
      (fields (field (name "MANUFACTURER") "Texas Instruments"))
      (libsource (lib "28PinArduino") (part "SN74AHC1G09DBVR"))
    )
    (comp (ref "U5")
      (value "SN74AHC1G09DBVR")
      (footprint "DBV_SOD235")
      (description "TEXAS INSTRUMENTS - SN74AHC1G09DBVR - AND Gate, 74AHC1G09, 2 Input, 2 V to 5.5 V, SOT-23-5")
      (fields (field (name "MANUFACTURER") "Texas Instruments"))
      (libsource (lib "28PinArduino") (part "SN74AHC1G09DBVR"))
    )
    (comp (ref "U6")
      (value "SN74AHC1G09DBVR")
      (footprint "DBV_SOD235")
      (description "TEXAS INSTRUMENTS - SN74AHC1G09DBVR - AND Gate, 74AHC1G09, 2 Input, 2 V to 5.5 V, SOT-23-5")
      (fields (field (name "MANUFACTURER") "Texas Instruments"))
      (libsource (lib "28PinArduino") (part "SN74AHC1G09DBVR"))
    )
    (comp (ref "U7")
      (value "SN74AHC1G09DBVR")
      (footprint "DBV_SOD235")
      (description "TEXAS INSTRUMENTS - SN74AHC1G09DBVR - AND Gate, 74AHC1G09, 2 Input, 2 V to 5.5 V, SOT-23-5")
      (fields (field (name "MANUFACTURER") "Texas Instruments"))
      (libsource (lib "28PinArduino") (part "SN74AHC1G09DBVR"))
    )
    (comp (ref "Y1")
      (value "ABM7-16MHZ")
      (footprint "AGM7_v1_1_big")
      (description "CRYSTAL 16.0000MHZ 18PF SMD")
      (fields
        (field (name "MANUFACTURER") "Abracon")
        (field (name "MANUFACTURER PART NUMBER") "ABM7-16.000MHZ-D2Y-T")
      )
      (libsource (lib "28PinArduino") (part "ABM7-16.000MHZ-D2Y-T"))
    )
    (comp (ref "Y2")
      (value "ABM7-16MHZ")
      (footprint "AGM7_v1_1_big")
      (description "CRYSTAL 16.0000MHZ 18PF SMD")
      (fields
        (field (name "MANUFACTURER") "Abracon")
        (field (name "MANUFACTURER PART NUMBER") "ABM7-16.000MHZ-D2Y-T")
      )
      (libsource (lib "28PinArduino") (part "ABM7-16.000MHZ-D2Y-T"))
    )
    (comp (ref "Z1")
      (value "CG0603MLC-05E")
      (footprint "RESC1608X06N")
      (description "VARISTOR 0603")
      (fields (field (name "MANUFACTURER") "Bourns") (field (name "VOLTAGE") "5V"))
      (libsource (lib "28PinArduino") (part "CG0603MLC-05E"))
    )
    (comp (ref "Z2")
      (value "CG0603MLC-05E")
      (footprint "RESC1608X06N")
      (description "VARISTOR 0603")
      (fields (field (name "MANUFACTURER") "Bourns") (field (name "VOLTAGE") "5V"))
      (libsource (lib "28PinArduino") (part "CG0603MLC-05E"))
    )
  )
  (nets
    (net (code "1") (name "+3V3") (class "Default")
      (node (ref "C13") (pin "2") (pinfunction "2_2") (pintype "passive"))
      (node (ref "C20") (pin "2") (pinfunction "2_2") (pintype "passive"))
      (node (ref "J8") (pin "4") (pinfunction "4_4") (pintype "passive"))
      (node (ref "JP2") (pin "3") (pinfunction "3_3") (pintype "passive"))
      (node (ref "R5") (pin "2") (pinfunction "2_2") (pintype "passive"))
      (node (ref "U2") (pin "4") (pinfunction "OUT_4") (pintype "passive"))
      (node (ref "U2") (pin "5") (pinfunction "SENSE_5") (pintype "passive"))
    )
    (net (code "2") (name "+5V") (class "Default")
      (node (ref "C12") (pin "2") (pinfunction "2_2") (pintype "passive"))
      (node (ref "C18") (pin "2") (pinfunction "2_2") (pintype "passive"))
      (node (ref "C4") (pin "2") (pinfunction "2_2") (pintype "passive"))
      (node (ref "C6") (pin "1") (pinfunction "1_1") (pintype "passive"))
      (node (ref "J5") (pin "1") (pinfunction "1_1") (pintype "passive"))
      (node (ref "J8") (pin "5") (pinfunction "5_5") (pintype "passive"))
      (node (ref "JP2") (pin "1") (pinfunction "1_1") (pintype "passive"))
      (node (ref "L1") (pin "2") (pinfunction "2_2") (pintype "passive"))
      (node (ref "R4") (pin "1") (pinfunction "1_1") (pintype "passive"))
      (node (ref "U1") (pin "32") (pinfunction "AVCC_32") (pintype "passive"))
      (node (ref "U2") (pin "1") (pinfunction "~{SHDN}_1") (pintype "passive"))
      (node (ref "U2") (pin "2") (pinfunction "IN_2") (pintype "passive"))
    )
    (net (code "3") (name "+5V{slash}3V3") (class "Default")
      (node (ref "C14") (pin "2") (pinfunction "2_2") (pintype "passive"))
      (node (ref "C19") (pin "2") (pinfunction "2_2") (pintype "passive"))
      (node (ref "C21") (pin "2") (pinfunction "2_2") (pintype "passive"))
      (node (ref "C26") (pin "1") (pinfunction "1_1") (pintype "passive"))
      (node (ref "C28") (pin "2") (pinfunction "2_2") (pintype "passive"))
      (node (ref "C29") (pin "2") (pinfunction "2_2") (pintype "passive"))
      (node (ref "C30") (pin "2") (pinfunction "2_2") (pintype "passive"))
      (node (ref "C7") (pin "2") (pinfunction "2_2") (pintype "passive"))
      (node (ref "D5") (pin "1") (pinfunction "Cathode_1") (pintype "passive"))
      (node (ref "D6") (pin "1") (pinfunction "Cathode_1") (pintype "passive"))
      (node (ref "FB1") (pin "1") (pinfunction "1_1") (pintype "passive"))
      (node (ref "FB2") (pin "1") (pinfunction "1_1") (pintype "passive"))
      (node (ref "FB3") (pin "1") (pinfunction "1_1") (pintype "passive"))
      (node (ref "J2") (pin "2") (pinfunction "2_2") (pintype "passive"))
      (node (ref "J4") (pin "2") (pinfunction "2_2") (pintype "passive"))
      (node (ref "J8") (pin "2") (pinfunction "2_2") (pintype "passive"))
      (node (ref "JP2") (pin "2") (pinfunction "2_2") (pintype "passive"))
      (node (ref "R1") (pin "2") (pinfunction "2_2") (pintype "passive"))
      (node (ref "R17") (pin "2") (pinfunction "2_2") (pintype "passive"))
      (node (ref "R18") (pin "2") (pinfunction "2_2") (pintype "passive"))
      (node (ref "R2") (pin "2") (pinfunction "2_2") (pintype "passive"))
      (node (ref "R20") (pin "2") (pinfunction "2_2") (pintype "passive"))
      (node (ref "R21") (pin "2") (pinfunction "2_2") (pintype "passive"))
      (node (ref "R22") (pin "2") (pinfunction "2_2") (pintype "passive"))
      (node (ref "R23") (pin "2") (pinfunction "2_2") (pintype "passive"))
      (node (ref "R24") (pin "2") (pinfunction "2_2") (pintype "passive"))
      (node (ref "R3") (pin "2") (pinfunction "2_2") (pintype "passive"))
      (node (ref "R4") (pin "2") (pinfunction "2_2") (pintype "passive"))
      (node (ref "R5") (pin "1") (pinfunction "1_1") (pintype "passive"))
      (node (ref "R6") (pin "2") (pinfunction "2_2") (pintype "passive"))
      (node (ref "U4") (pin "5") (pinfunction "5_5") (pintype "passive"))
      (node (ref "U5") (pin "5") (pinfunction "5_5") (pintype "passive"))
      (node (ref "U6") (pin "5") (pinfunction "5_5") (pintype "passive"))
      (node (ref "U7") (pin "5") (pinfunction "5_5") (pintype "passive"))
    )
    (net (code "4") (name "+AREF") (class "Default")
      (node (ref "C15") (pin "2") (pinfunction "2_2") (pintype "passive"))
      (node (ref "C24") (pin "2") (pinfunction "2_2") (pintype "passive"))
      (node (ref "J6") (pin "8") (pinfunction "8_8") (pintype "passive"))
      (node (ref "U3") (pin "21") (pinfunction "AVREF_21") (pintype "passive"))
    )
    (net (code "5") (name "/+3V3_16U2_UCAP") (class "Default")
      (node (ref "C8") (pin "2") (pinfunction "2_2") (pintype "passive"))
      (node (ref "R7") (pin "1") (pinfunction "1_1") (pintype "passive"))
      (node (ref "U1") (pin "27") (pinfunction "UCAP_27") (pintype "passive"))
    )
    (net (code "6") (name "/+5V_USB") (class "Default")
      (node (ref "C5") (pin "1") (pinfunction "1_1") (pintype "passive"))
      (node (ref "J3") (pin "1") (pinfunction "1_1") (pintype "passive"))
      (node (ref "L1") (pin "1") (pinfunction "1_1") (pintype "passive"))
    )
    (net (code "7") (name "/+5V{slash}3V3_16U2_UCAP") (class "Default")
      (node (ref "C1") (pin "2") (pinfunction "2_2") (pintype "passive"))
      (node (ref "C2") (pin "2") (pinfunction "2_2") (pintype "passive"))
      (node (ref "C3") (pin "2") (pinfunction "2_2") (pintype "passive"))
      (node (ref "FB1") (pin "2") (pinfunction "2_2") (pintype "passive"))
      (node (ref "R7") (pin "2") (pinfunction "2_2") (pintype "passive"))
      (node (ref "U1") (pin "31") (pinfunction "UVCC_31") (pintype "passive"))
      (node (ref "U1") (pin "4") (pinfunction "VCC_4") (pintype "passive"))
    )
    (net (code "8") (name "/+5V{slash}3V3_328P_AVCC") (class "Default")
      (node (ref "C22") (pin "2") (pinfunction "2_2") (pintype "passive"))
      (node (ref "C23") (pin "1") (pinfunction "1_1") (pintype "passive"))
      (node (ref "FB3") (pin "2") (pinfunction "2_2") (pintype "passive"))
      (node (ref "U3") (pin "20") (pinfunction "AVCC_20") (pintype "passive"))
    )
    (net (code "9") (name "/+5V{slash}3V3_328P_VCC") (class "Default")
      (node (ref "C16") (pin "2") (pinfunction "2_2") (pintype "passive"))
      (node (ref "C17") (pin "2") (pinfunction "2_2") (pintype "passive"))
      (node (ref "FB2") (pin "2") (pinfunction "2_2") (pintype "passive"))
      (node (ref "U3") (pin "7") (pinfunction "VCC_7") (pintype "passive"))
    )
    (net (code "10") (name "/16U2_16MHZ_XTAL1") (class "Default")
      (node (ref "C11") (pin "2") (pinfunction "2_2") (pintype "passive"))
      (node (ref "R12") (pin "1") (pinfunction "1_1") (pintype "passive"))
      (node (ref "U1") (pin "1") (pinfunction "XTAL1_1") (pintype "passive"))
    )
    (net (code "11") (name "/16U2_16MHZ_XTAL2") (class "Default")
      (node (ref "C9") (pin "2") (pinfunction "2_2") (pintype "passive"))
      (node (ref "R12") (pin "2") (pinfunction "2_2") (pintype "passive"))
      (node (ref "U1") (pin "2") (pinfunction "XTAL2/PC0_2") (pintype "passive"))
    )
    (net (code "12") (name "/16U2_328P_RESETn") (class "Default")
      (node (ref "D1") (pin "1") (pinfunction "Cathode_1") (pintype "passive"))
      (node (ref "D2") (pin "1") (pinfunction "Cathode_1") (pintype "passive"))
      (node (ref "JP3") (pin "2") (pinfunction "2_2") (pintype "passive"))
      (node (ref "R1") (pin "1") (pinfunction "1_1") (pintype "passive"))
      (node (ref "U1") (pin "10") (pinfunction "(INT5/_AIN3)_PD4_10") (pintype "passive"))
      (node (ref "U1") (pin "11") (pinfunction "(XCK_/_AIN4_/_PCINT12)_PD5_11") (pintype "passive"))
      (node (ref "U1") (pin "13") (pinfunction "(~{CTS}_/_~{HWB}_/_AIN6_/_T0_/_INT7)_PD7_13") (pintype "passive"))
    )
    (net (code "13") (name "/16U2_BUF_RESETn") (class "Default")
      (node (ref "C33") (pin "2") (pinfunction "2_2") (pintype "passive"))
      (node (ref "R28") (pin "2") (pinfunction "2_2") (pintype "passive"))
      (node (ref "U7") (pin "1") (pinfunction "1_1") (pintype "passive"))
      (node (ref "U7") (pin "2") (pinfunction "2_2") (pintype "passive"))
    )
    (net (code "14") (name "/16U2_HDR_RESETn") (class "Default")
      (node (ref "J2") (pin "5") (pinfunction "5_5") (pintype "passive"))
      (node (ref "JP1") (pin "3") (pinfunction "3_3") (pintype "passive"))
    )
    (net (code "15") (name "/16U2_MISO") (class "Default")
      (node (ref "J2") (pin "1") (pinfunction "1_1") (pintype "passive"))
      (node (ref "U1") (pin "17") (pinfunction "PB3_(PDO_/_MISO_/_PCINT3)_17") (pintype "passive"))
    )
    (net (code "16") (name "/16U2_MOSI") (class "Default")
      (node (ref "J2") (pin "4") (pinfunction "4_4") (pintype "passive"))
      (node (ref "U1") (pin "16") (pinfunction "(PDI_/_MOSI_/_PCINT2)_PB2_16") (pintype "passive"))
    )
    (net (code "17") (name "/16U2_PB4") (class "Default")
      (node (ref "J1") (pin "1") (pinfunction "1_1") (pintype "passive"))
      (node (ref "JP1") (pin "2") (pinfunction "2_2") (pintype "passive"))
      (node (ref "U1") (pin "18") (pinfunction "PB4_(T1_/_PCINT4)_18") (pintype "passive"))
    )
    (net (code "18") (name "/16U2_PB5") (class "Default")
      (node (ref "J1") (pin "3") (pinfunction "3_3") (pintype "passive"))
      (node (ref "U1") (pin "19") (pinfunction "PB5_(PCINT5)_19") (pintype "passive"))
    )
    (net (code "19") (name "/16U2_PB6") (class "Default")
      (node (ref "J1") (pin "2") (pinfunction "2_2") (pintype "passive"))
      (node (ref "U1") (pin "20") (pinfunction "PB6_(PCINT6)_20") (pintype "passive"))
    )
    (net (code "20") (name "/16U2_PB7") (class "Default")
      (node (ref "J1") (pin "4") (pinfunction "4_4") (pintype "passive"))
      (node (ref "U1") (pin "21") (pinfunction "PB7_(PCINT7_/_OC.0A_/_OC.1C)_21") (pintype "passive"))
    )
    (net (code "21") (name "/16U2_RESETn") (class "Default")
      (node (ref "JP1") (pin "4") (pinfunction "4_4") (pintype "passive"))
      (node (ref "R6") (pin "1") (pinfunction "1_1") (pintype "passive"))
      (node (ref "U1") (pin "24") (pinfunction "~{RESET}_(PC1_/_dW)_24") (pintype "passive"))
      (node (ref "U7") (pin "4") (pinfunction "4_4") (pintype "passive"))
    )
    (net (code "22") (name "/16U2_RXD") (class "Default")
      (node (ref "R14") (pin "1") (pinfunction "1_1") (pintype "passive"))
      (node (ref "U1") (pin "8") (pinfunction "(RXD1_/_AIN1_/_INT2)_PD2_8") (pintype "passive"))
    )
    (net (code "23") (name "/16U2_SCLK") (class "Default")
      (node (ref "J2") (pin "3") (pinfunction "3_3") (pintype "passive"))
      (node (ref "R8") (pin "2") (pinfunction "2_2") (pintype "passive"))
    )
    (net (code "24") (name "/16U2_SCLK_R") (class "Default")
      (node (ref "R8") (pin "1") (pinfunction "1_1") (pintype "passive"))
      (node (ref "U1") (pin "15") (pinfunction "(SCLK_/_PCINT1)_PB1_15") (pintype "passive"))
    )
    (net (code "25") (name "/16U2_TXD") (class "Default")
      (node (ref "R13") (pin "1") (pinfunction "1_1") (pintype "passive"))
      (node (ref "U1") (pin "9") (pinfunction "(TXD1_/_INT3)_PD3_9") (pintype "passive"))
    )
    (net (code "26") (name "/328P_16MHZ_XTAL1") (class "Default")
      (node (ref "C27") (pin "2") (pinfunction "2_2") (pintype "passive"))
      (node (ref "R19") (pin "1") (pinfunction "1_1") (pintype "passive"))
      (node (ref "U3") (pin "9") (pinfunction "(PCINT6/XTAL1/TOSC1)_PB6_9") (pintype "passive"))
    )
    (net (code "27") (name "/328P_16MHZ_XTAL2") (class "Default")
      (node (ref "C25") (pin "2") (pinfunction "2_2") (pintype "passive"))
      (node (ref "R19") (pin "2") (pinfunction "2_2") (pintype "passive"))
      (node (ref "U3") (pin "10") (pinfunction "(PCINT7/XTAL2/TOSC2)_PB7_10") (pintype "passive"))
    )
    (net (code "28") (name "/328P_AUTO_RESETn") (class "Default")
      (node (ref "C10") (pin "1") (pinfunction "1_1") (pintype "passive"))
      (node (ref "R22") (pin "1") (pinfunction "1_1") (pintype "passive"))
      (node (ref "U6") (pin "1") (pinfunction "1_1") (pintype "passive"))
    )
    (net (code "29") (name "/328P_BUF_RESETn") (class "Default")
      (node (ref "C32") (pin "2") (pinfunction "2_2") (pintype "passive"))
      (node (ref "R27") (pin "2") (pinfunction "2_2") (pintype "passive"))
      (node (ref "U6") (pin "2") (pinfunction "2_2") (pintype "passive"))
    )
    (net (code "30") (name "/328P_RESETn") (class "Default")
      (node (ref "J4") (pin "5") (pinfunction "5_5") (pintype "passive"))
      (node (ref "J8") (pin "3") (pinfunction "3_3") (pintype "passive"))
      (node (ref "JP1") (pin "1") (pinfunction "1_1") (pintype "passive"))
      (node (ref "R17") (pin "1") (pinfunction "1_1") (pintype "passive"))
      (node (ref "U3") (pin "1") (pinfunction "(PCINT14/~{RESET})_PC6_1") (pintype "passive"))
      (node (ref "U6") (pin "4") (pinfunction "4_4") (pintype "passive"))
    )
    (net (code "31") (name "/AD0") (class "Default")
      (node (ref "J9") (pin "1") (pinfunction "1_1") (pintype "passive"))
      (node (ref "U3") (pin "23") (pinfunction "PC0_(ADC0/PCINT8)_23") (pintype "passive"))
    )
    (net (code "32") (name "/AD1") (class "Default")
      (node (ref "J9") (pin "2") (pinfunction "2_2") (pintype "passive"))
      (node (ref "U3") (pin "24") (pinfunction "PC1_(ADC1/PCINT9)_24") (pintype "passive"))
    )
    (net (code "33") (name "/AD2") (class "Default")
      (node (ref "J9") (pin "3") (pinfunction "3_3") (pintype "passive"))
      (node (ref "U3") (pin "25") (pinfunction "PC2_(ADC2/PCINT10)_25") (pintype "passive"))
    )
    (net (code "34") (name "/AD3") (class "Default")
      (node (ref "J9") (pin "4") (pinfunction "4_4") (pintype "passive"))
      (node (ref "U3") (pin "26") (pinfunction "PC3_(ADC3/PCINT11)_26") (pintype "passive"))
    )
    (net (code "35") (name "/AD4{slash}SDA") (class "Default")
      (node (ref "J6") (pin "9") (pinfunction "9_9") (pintype "passive"))
      (node (ref "J9") (pin "5") (pinfunction "5_5") (pintype "passive"))
      (node (ref "U3") (pin "27") (pinfunction "PC4_(ADC4/SDA/PCINT12)_27") (pintype "passive"))
    )
    (net (code "36") (name "/AD5{slash}SCL") (class "Default")
      (node (ref "J6") (pin "10") (pinfunction "10_10") (pintype "passive"))
      (node (ref "J9") (pin "6") (pinfunction "6_6") (pintype "passive"))
      (node (ref "U3") (pin "28") (pinfunction "PC5_(ADC5/SCL/PCINT13)_28") (pintype "passive"))
    )
    (net (code "37") (name "/BUTTON_RESETn") (class "Default")
      (node (ref "D5") (pin "2") (pinfunction "Anode_2") (pintype "passive"))
      (node (ref "R23") (pin "1") (pinfunction "1_1") (pintype "passive"))
      (node (ref "R27") (pin "1") (pinfunction "1_1") (pintype "passive"))
      (node (ref "SW2") (pin "1") (pinfunction "1_1") (pintype "passive"))
      (node (ref "SW2") (pin "2") (pinfunction "2_2") (pintype "passive"))
    )
    (net (code "38") (name "/CON_USB_N") (class "Default")
      (node (ref "J3") (pin "2") (pinfunction "2_2") (pintype "passive"))
      (node (ref "R9") (pin "1") (pinfunction "1_1") (pintype "passive"))
      (node (ref "Z1") (pin "1") (pinfunction "1_1") (pintype "passive"))
    )
    (net (code "39") (name "/CON_USB_P") (class "Default")
      (node (ref "J3") (pin "3") (pinfunction "3_3") (pintype "passive"))
      (node (ref "R10") (pin "1") (pinfunction "1_1") (pintype "passive"))
      (node (ref "Z2") (pin "1") (pinfunction "1_1") (pintype "passive"))
    )
    (net (code "40") (name "/IO0") (class "Default")
      (node (ref "J10") (pin "8") (pinfunction "8_8") (pintype "passive"))
      (node (ref "R13") (pin "2") (pinfunction "2_2") (pintype "passive"))
      (node (ref "U3") (pin "2") (pinfunction "(PCINT16/RXD)_PD0_2") (pintype "passive"))
    )
    (net (code "41") (name "/IO1") (class "Default")
      (node (ref "J10") (pin "7") (pinfunction "7_7") (pintype "passive"))
      (node (ref "R14") (pin "2") (pinfunction "2_2") (pintype "passive"))
      (node (ref "U3") (pin "3") (pinfunction "(PCINT17/TXD)_PD1_3") (pintype "passive"))
    )
    (net (code "42") (name "/IO2") (class "Default")
      (node (ref "J10") (pin "6") (pinfunction "6_6") (pintype "passive"))
      (node (ref "U3") (pin "4") (pinfunction "(PCINT18/INT0)_PD2_4") (pintype "passive"))
    )
    (net (code "43") (name "/IO3") (class "Default")
      (node (ref "J10") (pin "5") (pinfunction "5_5") (pintype "passive"))
      (node (ref "U3") (pin "5") (pinfunction "(PCINT19/OC2B/INT1)_PD3_5") (pintype "passive"))
    )
    (net (code "44") (name "/IO4") (class "Default")
      (node (ref "J10") (pin "4") (pinfunction "4_4") (pintype "passive"))
      (node (ref "U3") (pin "6") (pinfunction "(PCINT20/XCK/T0)_PD4_6") (pintype "passive"))
    )
    (net (code "45") (name "/IO5") (class "Default")
      (node (ref "J10") (pin "3") (pinfunction "3_3") (pintype "passive"))
      (node (ref "U3") (pin "11") (pinfunction "(PCINT21/OC0B/T1)_PD5_11") (pintype "passive"))
    )
    (net (code "46") (name "/IO6") (class "Default")
      (node (ref "J10") (pin "2") (pinfunction "2_2") (pintype "passive"))
      (node (ref "U3") (pin "12") (pinfunction "(PCINT22/OC0A/AIN0)_PD6_12") (pintype "passive"))
    )
    (net (code "47") (name "/IO7") (class "Default")
      (node (ref "J10") (pin "1") (pinfunction "1_1") (pintype "passive"))
      (node (ref "U3") (pin "13") (pinfunction "(PCINT23/AIN1)_PD7_13") (pintype "passive"))
    )
    (net (code "48") (name "/IO8") (class "Default")
      (node (ref "J6") (pin "1") (pinfunction "1_1") (pintype "passive"))
      (node (ref "R25") (pin "2") (pinfunction "2_2") (pintype "passive"))
      (node (ref "U3") (pin "14") (pinfunction "(PCINT0/CLKO/ICP1)_PB0_14") (pintype "passive"))
    )
    (net (code "49") (name "/IO9") (class "Default")
      (node (ref "J6") (pin "2") (pinfunction "2_2") (pintype "passive"))
      (node (ref "U3") (pin "15") (pinfunction "PB1_(OC1A/PCINT1)_15") (pintype "passive"))
    )
    (net (code "50") (name "/MISO") (class "Default")
      (node (ref "J4") (pin "1") (pinfunction "1_1") (pintype "passive"))
      (node (ref "J6") (pin "5") (pinfunction "5_5") (pintype "passive"))
      (node (ref "U3") (pin "18") (pinfunction "PB4_(MISO/PCINT4)_18") (pintype "passive"))
    )
    (net (code "51") (name "/MOSI") (class "Default")
      (node (ref "J4") (pin "4") (pinfunction "4_4") (pintype "passive"))
      (node (ref "J6") (pin "4") (pinfunction "4_4") (pintype "passive"))
      (node (ref "U3") (pin "17") (pinfunction "PB3_(MOSI/OC2A/PCINT3)_17") (pintype "passive"))
    )
    (net (code "52") (name "/SCK") (class "Default")
      (node (ref "J4") (pin "3") (pinfunction "3_3") (pintype "passive"))
      (node (ref "J6") (pin "6") (pinfunction "6_6") (pintype "passive"))
      (node (ref "R16") (pin "2") (pinfunction "2_2") (pintype "passive"))
      (node (ref "U4") (pin "1") (pinfunction "1_1") (pintype "passive"))
      (node (ref "U4") (pin "2") (pinfunction "2_2") (pintype "passive"))
    )
    (net (code "53") (name "/SCK_R") (class "Default")
      (node (ref "R16") (pin "1") (pinfunction "1_1") (pintype "passive"))
      (node (ref "U3") (pin "19") (pinfunction "PB5_(SCK/PCINT5)_19") (pintype "passive"))
    )
    (net (code "54") (name "/SS") (class "Default")
      (node (ref "J6") (pin "3") (pinfunction "3_3") (pintype "passive"))
      (node (ref "U3") (pin "16") (pinfunction "PB2_(SS/OC1B/PCINT2)_16") (pintype "passive"))
    )
    (net (code "55") (name "/USB_N") (class "Default")
      (node (ref "R9") (pin "2") (pinfunction "2_2") (pintype "passive"))
      (node (ref "U1") (pin "30") (pinfunction "D-_30") (pintype "passive"))
    )
    (net (code "56") (name "/USB_P") (class "Default")
      (node (ref "R10") (pin "2") (pinfunction "2_2") (pintype "passive"))
      (node (ref "U1") (pin "29") (pinfunction "D+_29") (pintype "passive"))
    )
    (net (code "57") (name "/USER_BUTTON") (class "Default")
      (node (ref "R21") (pin "1") (pinfunction "1_1") (pintype "passive"))
      (node (ref "R26") (pin "1") (pinfunction "1_1") (pintype "passive"))
      (node (ref "SW1") (pin "1") (pinfunction "1_1") (pintype "passive"))
      (node (ref "SW1") (pin "2") (pinfunction "2_2") (pintype "passive"))
    )
    (net (code "58") (name "/USER_BUTTON_BUF") (class "Default")
      (node (ref "C31") (pin "2") (pinfunction "2_2") (pintype "passive"))
      (node (ref "R26") (pin "2") (pinfunction "2_2") (pintype "passive"))
      (node (ref "U5") (pin "1") (pinfunction "1_1") (pintype "passive"))
      (node (ref "U5") (pin "2") (pinfunction "2_2") (pintype "passive"))
    )
    (net (code "59") (name "GND") (class "Default")
      (node (ref "C1") (pin "1") (pinfunction "1_1") (pintype "passive"))
      (node (ref "C11") (pin "1") (pinfunction "1_1") (pintype "passive"))
      (node (ref "C12") (pin "1") (pinfunction "1_1") (pintype "passive"))
      (node (ref "C13") (pin "1") (pinfunction "1_1") (pintype "passive"))
      (node (ref "C14") (pin "1") (pinfunction "1_1") (pintype "passive"))
      (node (ref "C15") (pin "1") (pinfunction "1_1") (pintype "passive"))
      (node (ref "C16") (pin "1") (pinfunction "1_1") (pintype "passive"))
      (node (ref "C17") (pin "1") (pinfunction "1_1") (pintype "passive"))
      (node (ref "C18") (pin "1") (pinfunction "1_1") (pintype "passive"))
      (node (ref "C19") (pin "1") (pinfunction "1_1") (pintype "passive"))
      (node (ref "C2") (pin "1") (pinfunction "1_1") (pintype "passive"))
      (node (ref "C20") (pin "1") (pinfunction "1_1") (pintype "passive"))
      (node (ref "C21") (pin "1") (pinfunction "1_1") (pintype "passive"))
      (node (ref "C22") (pin "1") (pinfunction "1_1") (pintype "passive"))
      (node (ref "C23") (pin "2") (pinfunction "2_2") (pintype "passive"))
      (node (ref "C24") (pin "1") (pinfunction "1_1") (pintype "passive"))
      (node (ref "C25") (pin "1") (pinfunction "1_1") (pintype "passive"))
      (node (ref "C26") (pin "2") (pinfunction "2_2") (pintype "passive"))
      (node (ref "C27") (pin "1") (pinfunction "1_1") (pintype "passive"))
      (node (ref "C28") (pin "1") (pinfunction "1_1") (pintype "passive"))
      (node (ref "C29") (pin "1") (pinfunction "1_1") (pintype "passive"))
      (node (ref "C3") (pin "1") (pinfunction "1_1") (pintype "passive"))
      (node (ref "C30") (pin "1") (pinfunction "1_1") (pintype "passive"))
      (node (ref "C31") (pin "1") (pinfunction "1_1") (pintype "passive"))
      (node (ref "C32") (pin "1") (pinfunction "1_1") (pintype "passive"))
      (node (ref "C33") (pin "1") (pinfunction "1_1") (pintype "passive"))
      (node (ref "C4") (pin "1") (pinfunction "1_1") (pintype "passive"))
      (node (ref "C5") (pin "2") (pinfunction "2_2") (pintype "passive"))
      (node (ref "C6") (pin "2") (pinfunction "2_2") (pintype "passive"))
      (node (ref "C7") (pin "1") (pinfunction "1_1") (pintype "passive"))
      (node (ref "C8") (pin "1") (pinfunction "1_1") (pintype "passive"))
      (node (ref "C9") (pin "1") (pinfunction "1_1") (pintype "passive"))
      (node (ref "D4") (pin "1") (pinfunction "Cathode_1") (pintype "passive"))
      (node (ref "J2") (pin "6") (pinfunction "6_6") (pintype "passive"))
      (node (ref "J3") (pin "11") (pinfunction "11_11") (pintype "passive"))
      (node (ref "J3") (pin "5") (pinfunction "5_5") (pintype "passive"))
      (node (ref "J3") (pin "7") (pinfunction "7_7") (pintype "passive"))
      (node (ref "J3") (pin "9") (pinfunction "9_9") (pintype "passive"))
      (node (ref "J4") (pin "6") (pinfunction "6_6") (pintype "passive"))
      (node (ref "J6") (pin "7") (pinfunction "7_7") (pintype "passive"))
      (node (ref "J7") (pin "1") (pinfunction "1_1") (pintype "passive"))
      (node (ref "J8") (pin "6") (pinfunction "6_6") (pintype "passive"))
      (node (ref "J8") (pin "7") (pinfunction "7_7") (pintype "passive"))
      (node (ref "MH1") (pin "1") (pinfunction "1_1") (pintype "passive"))
      (node (ref "MH2") (pin "1") (pinfunction "1_1") (pintype "passive"))
      (node (ref "MH3") (pin "1") (pinfunction "1_1") (pintype "passive"))
      (node (ref "R11") (pin "2") (pinfunction "2_2") (pintype "passive"))
      (node (ref "R15") (pin "1") (pinfunction "1_1") (pintype "passive"))
      (node (ref "SW1") (pin "3") (pinfunction "3_3") (pintype "passive"))
      (node (ref "SW1") (pin "4") (pinfunction "4_4") (pintype "passive"))
      (node (ref "SW2") (pin "3") (pinfunction "3_3") (pintype "passive"))
      (node (ref "SW2") (pin "4") (pinfunction "4_4") (pintype "passive"))
      (node (ref "U1") (pin "28") (pinfunction "UGND_28") (pintype "passive"))
      (node (ref "U1") (pin "3") (pinfunction "GND_3") (pintype "passive"))
      (node (ref "U2") (pin "3") (pinfunction "GND_3") (pintype "passive"))
      (node (ref "U2") (pin "6") (pinfunction "EPAD_6") (pintype "passive"))
      (node (ref "U3") (pin "22") (pinfunction "AGND_22") (pintype "passive"))
      (node (ref "U3") (pin "8") (pinfunction "GND_8") (pintype "passive"))
      (node (ref "U4") (pin "3") (pinfunction "3_3") (pintype "passive"))
      (node (ref "U5") (pin "3") (pinfunction "3_3") (pintype "passive"))
      (node (ref "U6") (pin "3") (pinfunction "3_3") (pintype "passive"))
      (node (ref "U7") (pin "3") (pinfunction "3_3") (pintype "passive"))
      (node (ref "Z1") (pin "2") (pinfunction "2_2") (pintype "passive"))
      (node (ref "Z2") (pin "2") (pinfunction "2_2") (pintype "passive"))
    )
    (net (code "60") (name "Net-(C10-Pad2)") (class "Default")
      (node (ref "C10") (pin "2") (pinfunction "2_2") (pintype "passive"))
      (node (ref "JP3") (pin "1") (pinfunction "1_1") (pintype "passive"))
    )
    (net (code "61") (name "Net-(D1-Anode)") (class "Default")
      (node (ref "D1") (pin "2") (pinfunction "Anode_2") (pintype "passive"))
      (node (ref "R2") (pin "1") (pinfunction "1_1") (pintype "passive"))
    )
    (net (code "62") (name "Net-(D2-Anode)") (class "Default")
      (node (ref "D2") (pin "2") (pinfunction "Anode_2") (pintype "passive"))
      (node (ref "R3") (pin "1") (pinfunction "1_1") (pintype "passive"))
    )
    (net (code "63") (name "Net-(D3-Anode)") (class "Default")
      (node (ref "D3") (pin "2") (pinfunction "Anode_2") (pintype "passive"))
      (node (ref "R18") (pin "1") (pinfunction "1_1") (pintype "passive"))
    )
    (net (code "64") (name "Net-(D3-Cathode)") (class "Default")
      (node (ref "D3") (pin "1") (pinfunction "Cathode_1") (pintype "passive"))
      (node (ref "U4") (pin "4") (pinfunction "4_4") (pintype "passive"))
    )
    (net (code "65") (name "Net-(D4-Anode)") (class "Default")
      (node (ref "D4") (pin "2") (pinfunction "Anode_2") (pintype "passive"))
      (node (ref "R20") (pin "1") (pinfunction "1_1") (pintype "passive"))
    )
    (net (code "66") (name "Net-(D6-Anode)") (class "Default")
      (node (ref "D6") (pin "2") (pinfunction "Anode_2") (pintype "passive"))
      (node (ref "R24") (pin "1") (pinfunction "1_1") (pintype "passive"))
      (node (ref "R28") (pin "1") (pinfunction "1_1") (pintype "passive"))
    )
    (net (code "67") (name "Net-(J3-Pad4)") (class "Default")
      (node (ref "J3") (pin "4") (pinfunction "4_4") (pintype "passive"))
      (node (ref "R11") (pin "1") (pinfunction "1_1") (pintype "passive"))
    )
    (net (code "68") (name "Net-(JP3-Pad3)") (class "Default")
      (node (ref "JP3") (pin "3") (pinfunction "3_3") (pintype "passive"))
      (node (ref "R15") (pin "2") (pinfunction "2_2") (pintype "passive"))
    )
    (net (code "69") (name "Net-(R25-Pad1)") (class "Default")
      (node (ref "R25") (pin "1") (pinfunction "1_1") (pintype "passive"))
      (node (ref "U5") (pin "4") (pinfunction "4_4") (pintype "passive"))
    )
    (net (code "70") (name "unconnected-(J3-Pad6)") (class "Default")
      (node (ref "J3") (pin "6") (pinfunction "6_6") (pintype "passive"))
    )
    (net (code "71") (name "unconnected-(J3-Pad8)") (class "Default")
      (node (ref "J3") (pin "8") (pinfunction "8_8") (pintype "passive"))
    )
    (net (code "72") (name "unconnected-(J3-Pad10)") (class "Default")
      (node (ref "J3") (pin "10") (pinfunction "10_10") (pintype "passive"))
    )
    (net (code "73") (name "unconnected-(J8-Pad1)") (class "Default")
      (node (ref "J8") (pin "1") (pinfunction "1_1") (pintype "passive+no_connect"))
    )
    (net (code "74") (name "unconnected-(J8-Pad8)") (class "Default")
      (node (ref "J8") (pin "8") (pinfunction "8_8") (pintype "passive+no_connect"))
    )
    (net (code "75") (name "unconnected-(MH4-Pad1)") (class "Default")
      (node (ref "MH4") (pin "1") (pinfunction "1_1") (pintype "passive"))
    )
    (net (code "76") (name "unconnected-(U1-(AIN0_{slash}_INT1)_PD1-Pad7)") (class "Default")
      (node (ref "U1") (pin "7") (pinfunction "(AIN0_/_INT1)_PD1_7") (pintype "passive"))
    )
    (net (code "77") (name "unconnected-(U1-(OC.0B_{slash}_INT0)_PD0-Pad6)") (class "Default")
      (node (ref "U1") (pin "6") (pinfunction "(OC.0B_/_INT0)_PD0_6") (pintype "passive"))
    )
    (net (code "78") (name "unconnected-(U1-(PCINT11_{slash}_AIN2_)_PC2-Pad5)") (class "Default")
      (node (ref "U1") (pin "5") (pinfunction "(PCINT11_/_AIN2_)_PC2_5") (pintype "passive"))
    )
    (net (code "79") (name "unconnected-(U1-(SS_{slash}_PCINT0)_PB0-Pad14)") (class "Default")
      (node (ref "U1") (pin "14") (pinfunction "(SS_/_PCINT0)_PB0_14") (pintype "passive"))
    )
    (net (code "80") (name "unconnected-(U1-(~{RTS}_{slash}_AIN5_{slash}_INT6)_PD6-Pad12)") (class "Default")
      (node (ref "U1") (pin "12") (pinfunction "(~{RTS}_/_AIN5_/_INT6)_PD6_12") (pintype "passive+no_connect"))
    )
    (net (code "81") (name "unconnected-(U1-PC4_(PCINT10)-Pad26)") (class "Default")
      (node (ref "U1") (pin "26") (pinfunction "PC4_(PCINT10)_26") (pintype "passive"))
    )
    (net (code "82") (name "unconnected-(U1-PC5_(_PCINT9{slash}_OC.1B)-Pad25)") (class "Default")
      (node (ref "U1") (pin "25") (pinfunction "PC5_(_PCINT9/_OC.1B)_25") (pintype "passive"))
    )
    (net (code "83") (name "unconnected-(U1-PC6_(OC.1A_{slash}_PCINT8)-Pad23)") (class "Default")
      (node (ref "U1") (pin "23") (pinfunction "PC6_(OC.1A_/_PCINT8)_23") (pintype "passive"))
    )
    (net (code "84") (name "unconnected-(U1-PC7_(INT4_{slash}_ICP1_{slash}_CLKO)-Pad22)") (class "Default")
      (node (ref "U1") (pin "22") (pinfunction "PC7_(INT4_/_ICP1_/_CLKO)_22") (pintype "passive"))
    )
    (net (code "85") (name "unconnected-(Y1-Pad1)") (class "Default")
      (node (ref "Y1") (pin "1") (pinfunction "1_1") (pintype "passive"))
    )
    (net (code "86") (name "unconnected-(Y1-Pad2)") (class "Default")
      (node (ref "Y1") (pin "2") (pinfunction "2_2") (pintype "passive"))
    )
    (net (code "87") (name "unconnected-(Y2-Pad1)") (class "Default")
      (node (ref "Y2") (pin "1") (pinfunction "1_1") (pintype "passive"))
    )
    (net (code "88") (name "unconnected-(Y2-Pad2)") (class "Default")
      (node (ref "Y2") (pin "2") (pinfunction "2_2") (pintype "passive"))
    )
  )
)
